# Analogue_Input.net
KiCad netlist of a schematic drawn in Altium Designer
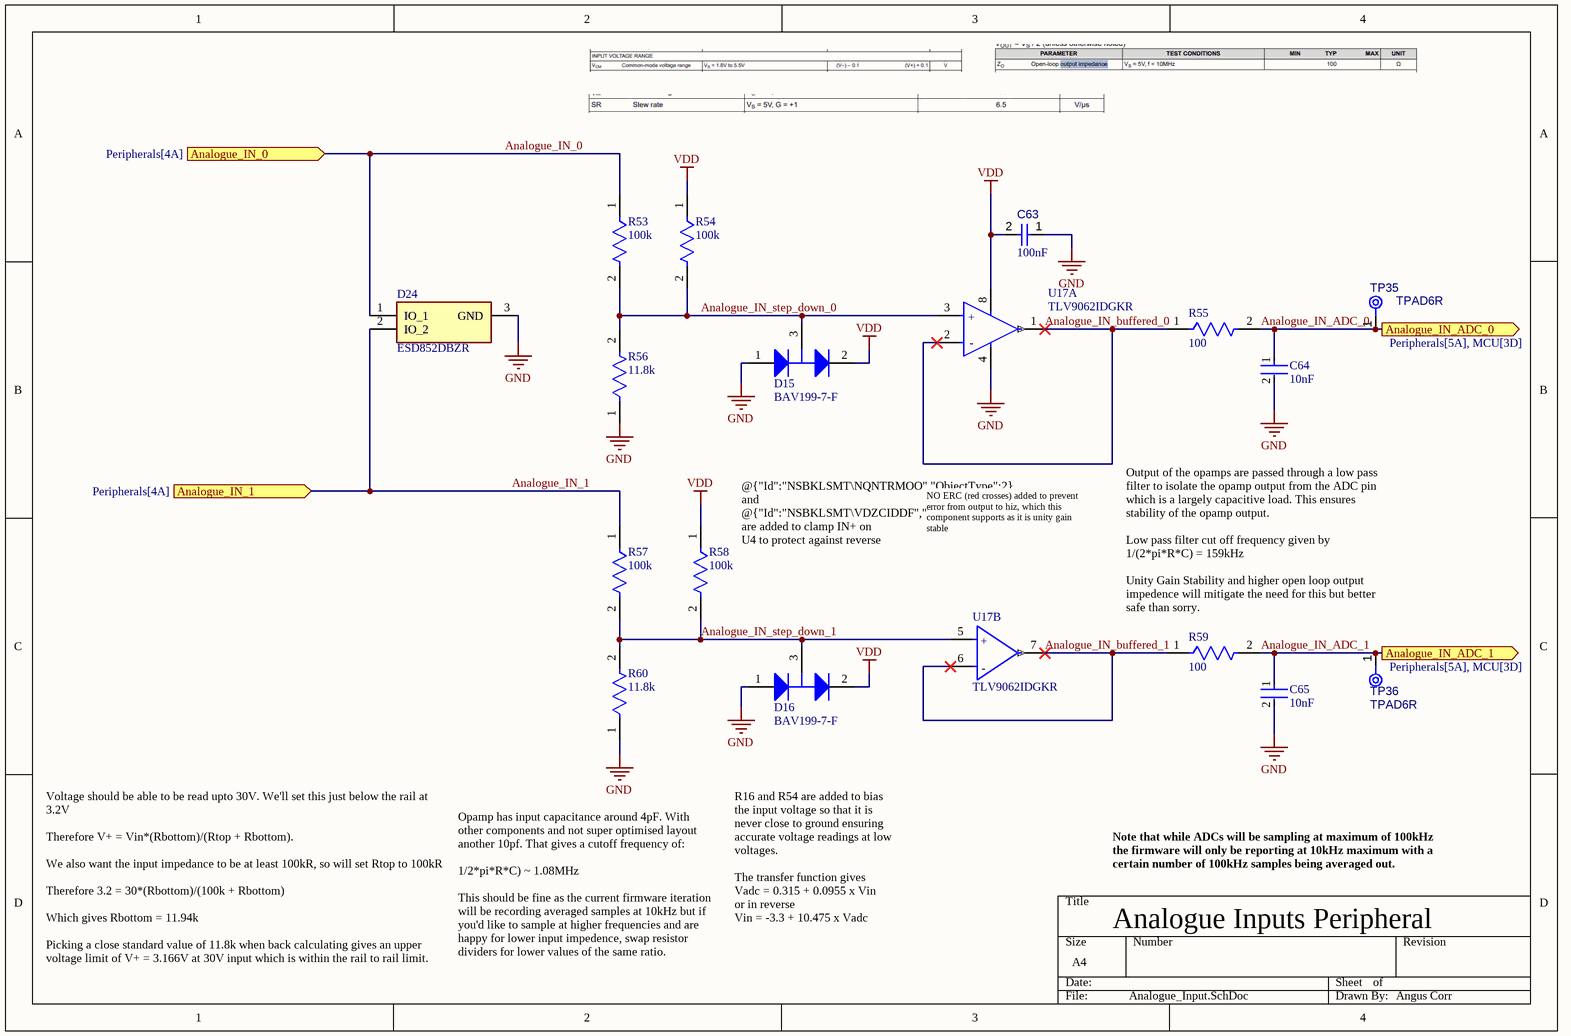
[diagram p0:  Analogue_Input.SchDoc]

(export (version "E")
  (design (tool "Eeschema 10.0.6"))
  (components
    (comp (ref "C63")
      (value "100nF")
      (footprint "CAPC1608X90X40NL10T20")
      (description "Chip Capacitor, 100 nF, +/- 10%, 50 V, 0603 (1608 Metric)")
      (fields (field (name "TOLERANCE") "10%") (field (name "Comment") "Capacitor 100 nF +/-10% 50 V 0603"))
      (libsource (lib "HIL RIG FYP") (part "CAP-NP-2"))
    )
    (comp (ref "C64")
      (value "10nF")
      (footprint "FP-CC0603-DA-IPC_B")
      (description "50V 10nF X7R ±10% 0603 Multilayer Ceramic Capacitors MLCC - SMD/SMT ROHS")
      (fields (field (name "VOLTAGE") "50V") (field (name "TOLERANCE") "10%"))
      (libsource (lib "HIL RIG FYP") (part "11868f565c42a9108669ba33697ecf6"))
    )
    (comp (ref "C65")
      (value "10nF")
      (footprint "FP-CC0603-DA-IPC_B")
      (description "50V 10nF X7R ±10% 0603 Multilayer Ceramic Capacitors MLCC - SMD/SMT ROHS")
      (fields (field (name "VOLTAGE") "50V") (field (name "TOLERANCE") "10%"))
      (libsource (lib "HIL RIG FYP") (part "11868f565c42a9108669ba33697ecf6"))
    )
    (comp (ref "D15")
      (value "BAV199-7-F")
      (footprint "DIOD-SOT23-3_A_V")
      (description "Diode Standard Recovery Rectifier 85 Volt 0.16A 3-Pin SOT-23 Tape and Reel")
      (libsource (lib "HIL RIG FYP") (part "D-AKC-3"))
    )
    (comp (ref "D16")
      (value "BAV199-7-F")
      (footprint "DIOD-SOT23-3_A_V")
      (description "Diode Standard Recovery Rectifier 85 Volt 0.16A 3-Pin SOT-23 Tape and Reel")
      (libsource (lib "HIL RIG FYP") (part "D-AKC-3"))
    )
    (comp (ref "D24")
      (value "ESD852DBZR")
      (footprint "SOT95P237X112-3N")
      (description "61V (Typ) Clamp 4.3A (8/20s) Ipp Tvs Diode Surface Mount SOT-23-3")
      (fields (field (name "MOUSER PART NUMBER") "595-ESD852DBZR"))
      (libsource (lib "HIL RIG FYP") (part "ESD852DBZR"))
    )
    (comp (ref "R53")
      (value "100k")
      (footprint "FP-RT0603-IPC_C")
      (description "100mW Thin Film Resistor 75V ±50ppm/℃ ±0.1% 100kΩ 0603 Chip Resistor - Surface Mount ROHS")
      (fields (field (name "TOLERANCE") "0.1%") (field (name "Comment") "RT0603BRE07100KL"))
      (libsource (lib "HIL RIG FYP") (part "1029c3af85768c4190bb7ad29bc67b5"))
    )
    (comp (ref "R54")
      (value "100k")
      (footprint "FP-RT0603-IPC_C")
      (description "100mW Thin Film Resistor 75V ±50ppm/℃ ±0.1% 100kΩ 0603 Chip Resistor - Surface Mount ROHS")
      (fields (field (name "TOLERANCE") "0.1%") (field (name "Comment") "RT0603BRE07100KL"))
      (libsource (lib "HIL RIG FYP") (part "1029c3af85768c4190bb7ad29bc67b5"))
    )
    (comp (ref "R55")
      (value "100")
      (footprint "FP-RT0603-IPC_C")
      (description "100mW Thin Film Resistor 75V ±25ppm/℃ ±0.1% 100Ω 0603 Chip Resistor - Surface Mount ROHS")
      (fields (field (name "TOLERANCE") "0.1%") (field (name "Comment") "RT0603BRD07100RL"))
      (libsource (lib "HIL RIG FYP") (part "1029c3af85768c4190bb7ad29bc67b5"))
    )
    (comp (ref "R56")
      (value "11.8k")
      (footprint "FP-RT0603-IPC_A")
      (description "100mW Thin Film Resistor ±25ppm/℃ ±0.1% 11.8kΩ 0603 Chip Resistor - Surface Mount ROHS")
      (fields (field (name "TOLERANCE") "0.1%") (field (name "Comment") "RT0603BRD0711K8L"))
      (libsource (lib "HIL RIG FYP") (part "1029c3af85768c4190bb7ad29bc67b5"))
    )
    (comp (ref "R57")
      (value "100k")
      (footprint "FP-RT0603-IPC_C")
      (description "100mW Thin Film Resistor 75V ±50ppm/℃ ±0.1% 100kΩ 0603 Chip Resistor - Surface Mount ROHS")
      (fields (field (name "TOLERANCE") "0.1%") (field (name "Comment") "RT0603BRE07100KL"))
      (libsource (lib "HIL RIG FYP") (part "1029c3af85768c4190bb7ad29bc67b5"))
    )
    (comp (ref "R58")
      (value "100k")
      (footprint "FP-RT0603-IPC_C")
      (description "100mW Thin Film Resistor 75V ±50ppm/℃ ±0.1% 100kΩ 0603 Chip Resistor - Surface Mount ROHS")
      (fields (field (name "TOLERANCE") "0.1%") (field (name "Comment") "RT0603BRE07100KL"))
      (libsource (lib "HIL RIG FYP") (part "1029c3af85768c4190bb7ad29bc67b5"))
    )
    (comp (ref "R59")
      (value "100")
      (footprint "FP-RT0603-IPC_C")
      (description "100mW Thin Film Resistor 75V ±25ppm/℃ ±0.1% 100Ω 0603 Chip Resistor - Surface Mount ROHS")
      (fields (field (name "TOLERANCE") "0.1%") (field (name "Comment") "RT0603BRD07100RL"))
      (libsource (lib "HIL RIG FYP") (part "1029c3af85768c4190bb7ad29bc67b5"))
    )
    (comp (ref "R60")
      (value "11.8k")
      (footprint "FP-RT0603-IPC_A")
      (description "100mW Thin Film Resistor ±25ppm/℃ ±0.1% 11.8kΩ 0603 Chip Resistor - Surface Mount ROHS")
      (fields (field (name "TOLERANCE") "0.1%") (field (name "Comment") "RT0603BRD0711K8L"))
      (libsource (lib "HIL RIG FYP") (part "1029c3af85768c4190bb7ad29bc67b5"))
    )
    (comp (ref "TP35")
      (value "TPAD6R")
      (footprint "TP06R")
      (description "0.6mm round")
      (libsource (lib "HIL RIG FYP") (part "CMP-001-0001-4"))
    )
    (comp (ref "TP36")
      (value "TPAD6R")
      (footprint "TP06R")
      (description "0.6mm round")
      (libsource (lib "HIL RIG FYP") (part "CMP-001-0001-4"))
    )
    (comp (ref "U17")
      (value "TLV9062IDGKR")
      (footprint "FP-DGK0008A-IPC_A")
      (description "Dual, 5.5-V, 10-MHz operational amplifier 8-VSSOP -40 to 125")
      (libsource (lib "HIL RIG FYP") (part "d5b36c1049528187b1d2197d5d58d7e"))
    )
  )
  (nets
    (net (code "1") (name "/Analogue_IN_0") (class "Default")
      (node (ref "D24") (pin "1") (pinfunction "IO_1_1") (pintype "passive"))
      (node (ref "R53") (pin "1") (pinfunction "1_1") (pintype "passive"))
    )
    (net (code "2") (name "/Analogue_IN_1") (class "Default")
      (node (ref "D24") (pin "2") (pinfunction "IO_2_2") (pintype "passive"))
      (node (ref "R57") (pin "1") (pinfunction "1_1") (pintype "passive"))
    )
    (net (code "3") (name "/Analogue_IN_ADC_0") (class "Default")
      (node (ref "C64") (pin "1") (pinfunction "1_1") (pintype "passive"))
      (node (ref "R55") (pin "2") (pinfunction "2_2") (pintype "passive"))
      (node (ref "TP35") (pin "1") (pinfunction "TP_1") (pintype "passive"))
    )
    (net (code "4") (name "/Analogue_IN_ADC_1") (class "Default")
      (node (ref "C65") (pin "1") (pinfunction "1_1") (pintype "passive"))
      (node (ref "R59") (pin "2") (pinfunction "2_2") (pintype "passive"))
      (node (ref "TP36") (pin "1") (pinfunction "TP_1") (pintype "passive"))
    )
    (net (code "5") (name "/Analogue_IN_buffered_0") (class "Default")
      (node (ref "R55") (pin "1") (pinfunction "1_1") (pintype "passive"))
      (node (ref "U17") (pin "1") (pinfunction "OUT1_1") (pintype "output"))
      (node (ref "U17") (pin "2") (pinfunction "IN1-_2") (pintype "tri_state"))
    )
    (net (code "6") (name "/Analogue_IN_buffered_1") (class "Default")
      (node (ref "R59") (pin "1") (pinfunction "1_1") (pintype "passive"))
      (node (ref "U17") (pin "6") (pinfunction "IN2-_6") (pintype "tri_state"))
      (node (ref "U17") (pin "7") (pinfunction "OUT2_7") (pintype "output"))
    )
    (net (code "7") (name "/Analogue_IN_step_down_0") (class "Default")
      (node (ref "D15") (pin "3") (pinfunction "C_3") (pintype "passive"))
      (node (ref "R53") (pin "2") (pinfunction "2_2") (pintype "passive"))
      (node (ref "R54") (pin "2") (pinfunction "2_2") (pintype "passive"))
      (node (ref "R56") (pin "2") (pinfunction "2_2") (pintype "passive"))
      (node (ref "U17") (pin "3") (pinfunction "IN1+_3") (pintype "tri_state"))
    )
    (net (code "8") (name "/Analogue_IN_step_down_1") (class "Default")
      (node (ref "D16") (pin "3") (pinfunction "C_3") (pintype "passive"))
      (node (ref "R57") (pin "2") (pinfunction "2_2") (pintype "passive"))
      (node (ref "R58") (pin "2") (pinfunction "2_2") (pintype "passive"))
      (node (ref "R60") (pin "2") (pinfunction "2_2") (pintype "passive"))
      (node (ref "U17") (pin "5") (pinfunction "IN2+_5") (pintype "tri_state"))
    )
    (net (code "9") (name "GND") (class "Default")
      (node (ref "C63") (pin "1") (pinfunction "1_1") (pintype "passive"))
      (node (ref "C64") (pin "2") (pinfunction "2_2") (pintype "passive"))
      (node (ref "C65") (pin "2") (pinfunction "2_2") (pintype "passive"))
      (node (ref "D15") (pin "1") (pinfunction "A_1") (pintype "passive"))
      (node (ref "D16") (pin "1") (pinfunction "A_1") (pintype "passive"))
      (node (ref "D24") (pin "3") (pinfunction "GND_3") (pintype "passive"))
      (node (ref "R56") (pin "1") (pinfunction "1_1") (pintype "passive"))
      (node (ref "R60") (pin "1") (pinfunction "1_1") (pintype "passive"))
      (node (ref "U17") (pin "4") (pinfunction "V-_4") (pintype "power_in"))
    )
    (net (code "10") (name "VDD") (class "Default")
      (node (ref "C63") (pin "2") (pinfunction "2_2") (pintype "passive"))
      (node (ref "D15") (pin "2") (pinfunction "K_2") (pintype "passive"))
      (node (ref "D16") (pin "2") (pinfunction "K_2") (pintype "passive"))
      (node (ref "R54") (pin "1") (pinfunction "1_1") (pintype "passive"))
      (node (ref "R58") (pin "1") (pinfunction "1_1") (pintype "passive"))
      (node (ref "U17") (pin "8") (pinfunction "V+_8") (pintype "power_in"))
    )
  )
)
